# beaconboard3.net
KiCad netlist of a schematic drawn in EAGLE
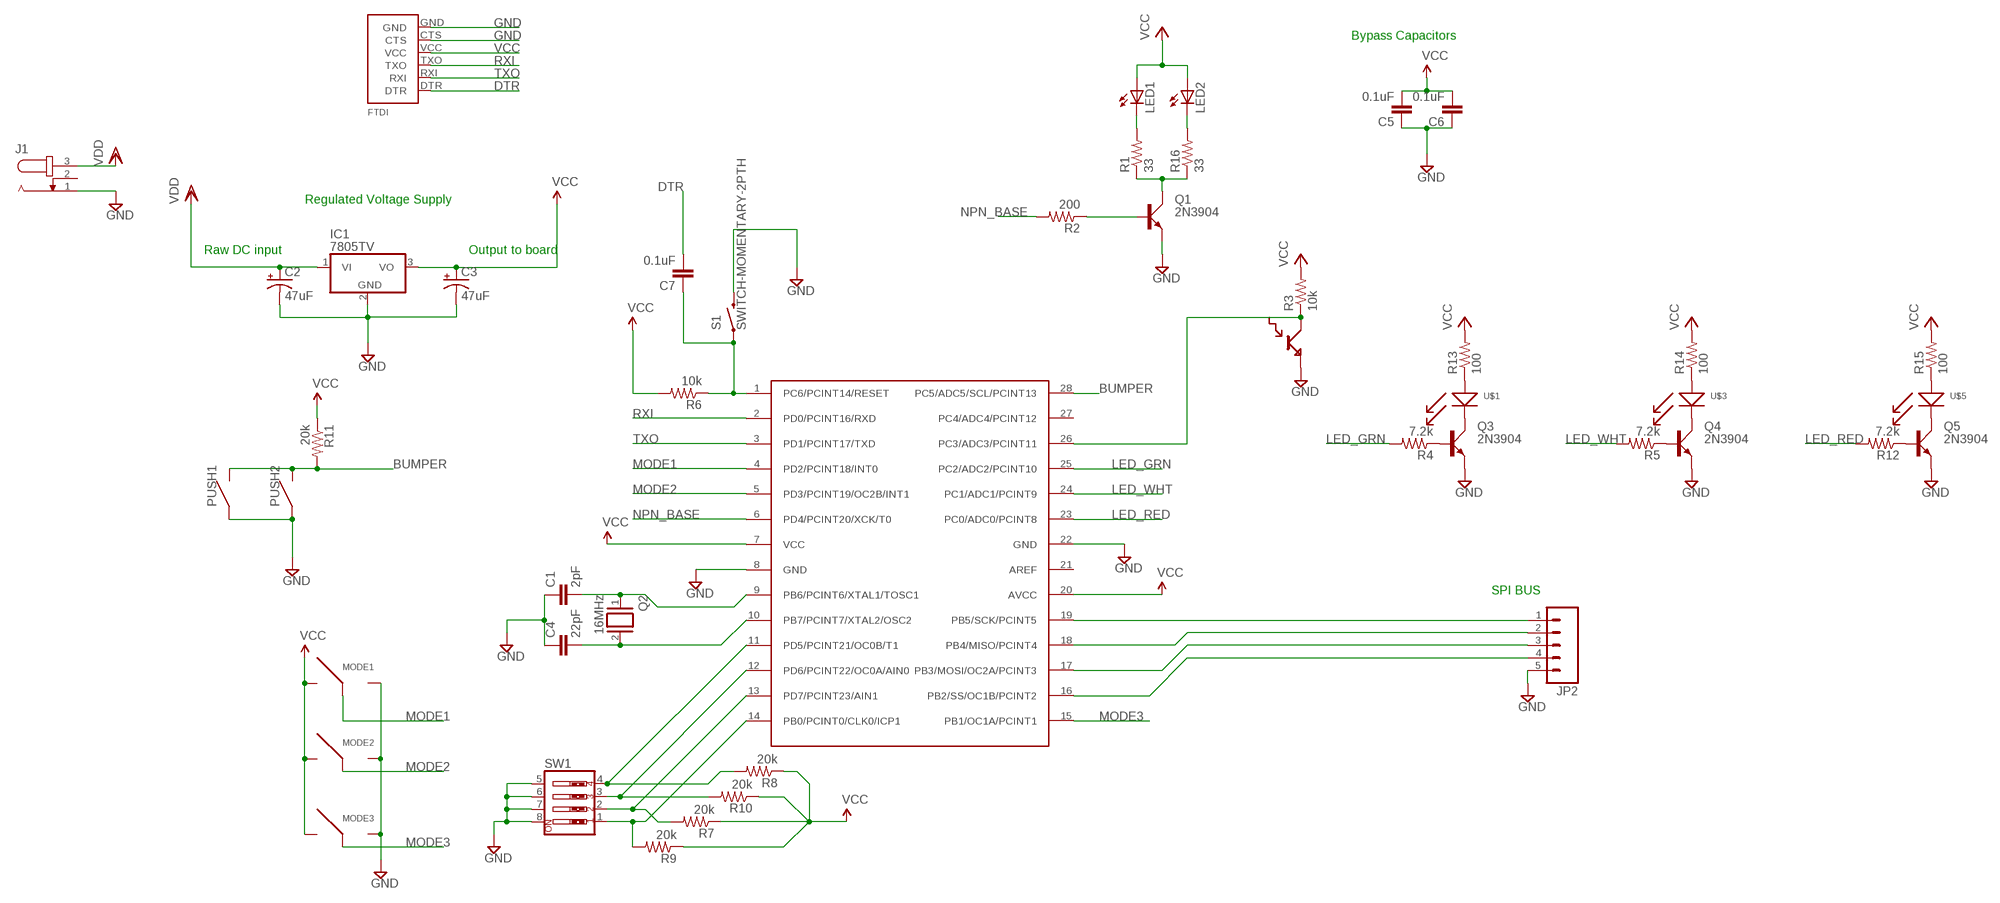
[diagram p0: schematic, sheet 1]

(export (version "E")
  (design (tool "Eeschema 10.0.6"))
  (components
    (comp (ref "C1")
      (value "2pF")
      (footprint "eagle-import:CAP-PTH-SMALL")
      (libsource (lib "eagle-import") (part "CAPPTH"))
    )
    (comp (ref "C2")
      (value "47uF")
      (footprint "eagle-import:CPOL-RADIAL-10UF-25V")
      (libsource (lib "eagle-import") (part "CAP_POLPTH2"))
    )
    (comp (ref "C3")
      (value "47uF")
      (footprint "eagle-import:CPOL-RADIAL-10UF-25V")
      (libsource (lib "eagle-import") (part "CAP_POLPTH2"))
    )
    (comp (ref "C4")
      (value "22pF")
      (footprint "eagle-import:CAP-PTH-SMALL")
      (libsource (lib "eagle-import") (part "CAPPTH"))
    )
    (comp (ref "C5")
      (value "0.1uF")
      (footprint "eagle-import:CAP-PTH-5MM")
      (libsource (lib "eagle-import") (part "CAPPTH1"))
    )
    (comp (ref "C6")
      (value "0.1uF")
      (footprint "eagle-import:CAP-PTH-5MM")
      (libsource (lib "eagle-import") (part "CAPPTH1"))
    )
    (comp (ref "C7")
      (value "0.1uF")
      (footprint "eagle-import:CAP-PTH-5MM")
      (libsource (lib "eagle-import") (part "CAPPTH1"))
    )
    (comp (ref "IC1")
      (value "7805TV")
      (footprint "eagle-import:TO220V")
      (libsource (lib "eagle-import") (part "78TV05"))
    )
    (comp (ref "J1")
      (value "JACK-PLUG1")
      (footprint "eagle-import:SPC4078")
      (libsource (lib "eagle-import") (part "JACK-PLUG1"))
    )
    (comp (ref "JP2")
      (value "M05LOCK_LONGPADS")
      (footprint "eagle-import:1X05_LOCK_LONGPADS")
      (libsource (lib "eagle-import") (part "M05LOCK_LONGPADS"))
    )
    (comp (ref "LED1")
      (value "LED-2AC-CP41B-WES")
      (footprint "eagle-import:CP41B")
      (libsource (lib "eagle-import") (part "LED-2AC-CP41B-WES"))
    )
    (comp (ref "LED2")
      (value "LED-2AC-CP41B-WES")
      (footprint "eagle-import:CP41B")
      (libsource (lib "eagle-import") (part "LED-2AC-CP41B-WES"))
    )
    (comp (ref "MODE1")
      (value "SPD_SLIDE_SWITCH")
      (footprint "eagle-import:SPDT_SLIDE_SWITCH")
      (libsource (lib "eagle-import") (part "SPD_SLIDE_SWITCH"))
    )
    (comp (ref "MODE2")
      (value "SPD_SLIDE_SWITCH")
      (footprint "eagle-import:SPDT_SLIDE_SWITCH")
      (libsource (lib "eagle-import") (part "SPD_SLIDE_SWITCH"))
    )
    (comp (ref "MODE3")
      (value "SPD_SLIDE_SWITCH")
      (footprint "eagle-import:SPDT_SLIDE_SWITCH")
      (libsource (lib "eagle-import") (part "SPD_SLIDE_SWITCH"))
    )
    (comp (ref "PUSH1")
      (value "D6_PUSHBUTTON")
      (footprint "eagle-import:D6_PUSH_BUTTON")
      (libsource (lib "eagle-import") (part "D6_PUSHBUTTON"))
    )
    (comp (ref "PUSH2")
      (value "D6_PUSHBUTTON")
      (footprint "eagle-import:D6_PUSH_BUTTON")
      (libsource (lib "eagle-import") (part "D6_PUSHBUTTON"))
    )
    (comp (ref "Q1")
      (value "2N3904")
      (footprint "eagle-import:TO92D")
      (libsource (lib "eagle-import") (part "2N3904"))
    )
    (comp (ref "Q2")
      (value "16MHz")
      (footprint "eagle-import:QS")
      (libsource (lib "eagle-import") (part "XTAL/S"))
    )
    (comp (ref "Q3")
      (value "2N3904")
      (footprint "eagle-import:TO92D")
      (libsource (lib "eagle-import") (part "2N3904"))
    )
    (comp (ref "Q4")
      (value "2N3904")
      (footprint "eagle-import:TO92D")
      (libsource (lib "eagle-import") (part "2N3904"))
    )
    (comp (ref "Q5")
      (value "2N3904")
      (footprint "eagle-import:TO92D")
      (libsource (lib "eagle-import") (part "2N3904"))
    )
    (comp (ref "R1")
      (value "33")
      (footprint "eagle-import:AXIAL-0.4")
      (libsource (lib "eagle-import") (part "RESISTORPTH-1/4W"))
    )
    (comp (ref "R2")
      (value "200")
      (footprint "eagle-import:AXIAL-0.4")
      (libsource (lib "eagle-import") (part "RESISTORPTH-1/4W"))
    )
    (comp (ref "R3")
      (value "10k")
      (footprint "eagle-import:AXIAL-0.4")
      (libsource (lib "eagle-import") (part "RESISTORPTH-1/4W"))
    )
    (comp (ref "R4")
      (value "7.2k")
      (footprint "eagle-import:AXIAL-0.4")
      (libsource (lib "eagle-import") (part "RESISTORPTH-1/4W"))
    )
    (comp (ref "R5")
      (value "7.2k")
      (footprint "eagle-import:AXIAL-0.4")
      (libsource (lib "eagle-import") (part "RESISTORPTH-1/4W"))
    )
    (comp (ref "R6")
      (value "10k")
      (footprint "eagle-import:AXIAL-0.4")
      (libsource (lib "eagle-import") (part "RESISTORPTH-1/4W"))
    )
    (comp (ref "R7")
      (value "20k")
      (footprint "eagle-import:AXIAL-0.4")
      (libsource (lib "eagle-import") (part "RESISTORPTH-1/4W"))
    )
    (comp (ref "R8")
      (value "20k")
      (footprint "eagle-import:AXIAL-0.4")
      (libsource (lib "eagle-import") (part "RESISTORPTH-1/4W"))
    )
    (comp (ref "R9")
      (value "20k")
      (footprint "eagle-import:AXIAL-0.4")
      (libsource (lib "eagle-import") (part "RESISTORPTH-1/4W"))
    )
    (comp (ref "R10")
      (value "20k")
      (footprint "eagle-import:AXIAL-0.4")
      (libsource (lib "eagle-import") (part "RESISTORPTH-1/4W"))
    )
    (comp (ref "R11")
      (value "20k")
      (footprint "eagle-import:AXIAL-0.4")
      (libsource (lib "eagle-import") (part "RESISTORPTH-1/4W"))
    )
    (comp (ref "R12")
      (value "7.2k")
      (footprint "eagle-import:AXIAL-0.4")
      (libsource (lib "eagle-import") (part "RESISTORPTH-1/4W"))
    )
    (comp (ref "R13")
      (value "100")
      (footprint "eagle-import:AXIAL-0.4")
      (libsource (lib "eagle-import") (part "RESISTORPTH-1/4W"))
    )
    (comp (ref "R14")
      (value "100")
      (footprint "eagle-import:AXIAL-0.4")
      (libsource (lib "eagle-import") (part "RESISTORPTH-1/4W"))
    )
    (comp (ref "R15")
      (value "100")
      (footprint "eagle-import:AXIAL-0.4")
      (libsource (lib "eagle-import") (part "RESISTORPTH-1/4W"))
    )
    (comp (ref "R16")
      (value "33")
      (footprint "eagle-import:AXIAL-0.4")
      (libsource (lib "eagle-import") (part "RESISTORPTH-1/4W"))
    )
    (comp (ref "S1")
      (value "SWITCH-MOMENTARY-2PTH")
      (footprint "eagle-import:TACTILE-PTH")
      (libsource (lib "eagle-import") (part "SWITCH-MOMENTARY-2PTH"))
    )
    (comp (ref "SW1")
      (value "SW_DIP-4")
      (footprint "eagle-import:EDG-04")
      (libsource (lib "eagle-import") (part "SW_DIP-4"))
    )
    (comp (ref "U$1")
      (value "8MM_LED")
      (footprint "eagle-import:8MM_LED")
      (libsource (lib "eagle-import") (part "8MM_LED"))
    )
    (comp (ref "U$2")
      (value "BPW77NA")
      (footprint "eagle-import:TO-18")
      (libsource (lib "eagle-import") (part "BPW77NA"))
    )
    (comp (ref "U$3")
      (value "8MM_LED")
      (footprint "eagle-import:8MM_LED")
      (libsource (lib "eagle-import") (part "8MM_LED"))
    )
    (comp (ref "U$4")
      (value "ATMEGA328")
      (footprint "eagle-import:DIL28-3")
      (libsource (lib "eagle-import") (part "ATMEGA328"))
    )
    (comp (ref "U$5")
      (value "8MM_LED")
      (footprint "eagle-import:8MM_LED")
      (libsource (lib "eagle-import") (part "8MM_LED"))
    )
    (comp (ref "U$6")
      (value "FTDI")
      (footprint "eagle-import:FTDI")
      (libsource (lib "eagle-import") (part "FTDI"))
    )
  )
  (nets
    (net (code "1") (name "/BUMPER") (class "Default")
      (node (ref "PUSH1") (pin "3") (pinfunction "2_3") (pintype "bidirectional"))
      (node (ref "PUSH1") (pin "4") (pinfunction "2_4") (pintype "bidirectional"))
      (node (ref "PUSH2") (pin "3") (pinfunction "2_3") (pintype "bidirectional"))
      (node (ref "PUSH2") (pin "4") (pinfunction "2_4") (pintype "bidirectional"))
      (node (ref "R11") (pin "P$2") (pinfunction "2_P$2") (pintype "passive"))
      (node (ref "U$4") (pin "28") (pinfunction "PC5/ADC5/SCL/PCINT13_28") (pintype "bidirectional"))
    )
    (net (code "2") (name "/DTR") (class "Default")
      (node (ref "C7") (pin "2") (pinfunction "2_2") (pintype "passive"))
      (node (ref "U$6") (pin "DTR") (pinfunction "DTR_DTR") (pintype "bidirectional"))
    )
    (net (code "3") (name "/LED_GRN") (class "Default")
      (node (ref "R4") (pin "P$2") (pinfunction "2_P$2") (pintype "passive"))
      (node (ref "U$4") (pin "25") (pinfunction "PC2/ADC2/PCINT10_25") (pintype "bidirectional"))
    )
    (net (code "4") (name "/LED_RED") (class "Default")
      (node (ref "R12") (pin "P$2") (pinfunction "2_P$2") (pintype "passive"))
      (node (ref "U$4") (pin "23") (pinfunction "PC0/ADC0/PCINT8_23") (pintype "bidirectional"))
    )
    (net (code "5") (name "/LED_WHT") (class "Default")
      (node (ref "R5") (pin "P$2") (pinfunction "2_P$2") (pintype "passive"))
      (node (ref "U$4") (pin "24") (pinfunction "PC1/ADC1/PCINT9_24") (pintype "bidirectional"))
    )
    (net (code "6") (name "/MODE1") (class "Default")
      (node (ref "MODE1") (pin "2") (pinfunction "2_2") (pintype "bidirectional"))
      (node (ref "U$4") (pin "4") (pinfunction "PD2/PCINT18/INT0_4") (pintype "bidirectional"))
    )
    (net (code "7") (name "/MODE2") (class "Default")
      (node (ref "MODE2") (pin "2") (pinfunction "2_2") (pintype "bidirectional"))
      (node (ref "U$4") (pin "5") (pinfunction "PD3/PCINT19/OC2B/INT1_5") (pintype "bidirectional"))
    )
    (net (code "8") (name "/MODE3") (class "Default")
      (node (ref "MODE3") (pin "2") (pinfunction "2_2") (pintype "bidirectional"))
      (node (ref "U$4") (pin "15") (pinfunction "PB1/OC1A/PCINT1_15") (pintype "bidirectional"))
    )
    (net (code "9") (name "/NPN_BASE") (class "Default")
      (node (ref "R2") (pin "P$2") (pinfunction "2_P$2") (pintype "passive"))
      (node (ref "U$4") (pin "6") (pinfunction "PD4/PCINT20/XCK/T0_6") (pintype "bidirectional"))
    )
    (net (code "10") (name "/RXI") (class "Default")
      (node (ref "U$4") (pin "2") (pinfunction "PD0/PCINT16/RXD_2") (pintype "bidirectional"))
      (node (ref "U$6") (pin "TXO") (pinfunction "TXO_TXO") (pintype "bidirectional"))
    )
    (net (code "11") (name "/TXO") (class "Default")
      (node (ref "U$4") (pin "3") (pinfunction "PD1/PCINT17/TXD_3") (pintype "bidirectional"))
      (node (ref "U$6") (pin "RXI") (pinfunction "RXI_RXI") (pintype "bidirectional"))
    )
    (net (code "12") (name "GND") (class "Default")
      (node (ref "C1") (pin "1") (pinfunction "1_1") (pintype "passive"))
      (node (ref "C2") (pin "2") (pinfunction "-_2") (pintype "passive"))
      (node (ref "C3") (pin "2") (pinfunction "-_2") (pintype "passive"))
      (node (ref "C4") (pin "1") (pinfunction "1_1") (pintype "passive"))
      (node (ref "C5") (pin "1") (pinfunction "1_1") (pintype "passive"))
      (node (ref "C6") (pin "1") (pinfunction "1_1") (pintype "passive"))
      (node (ref "IC1") (pin "2") (pinfunction "GND_2") (pintype "passive"))
      (node (ref "J1") (pin "1") (pinfunction "1_1") (pintype "passive"))
      (node (ref "JP2") (pin "5") (pinfunction "5_5") (pintype "passive"))
      (node (ref "MODE1") (pin "3") (pinfunction "3_3") (pintype "bidirectional"))
      (node (ref "MODE2") (pin "3") (pinfunction "3_3") (pintype "bidirectional"))
      (node (ref "MODE3") (pin "3") (pinfunction "3_3") (pintype "bidirectional"))
      (node (ref "PUSH1") (pin "1") (pinfunction "1_1") (pintype "bidirectional"))
      (node (ref "PUSH1") (pin "2") (pinfunction "1_2") (pintype "bidirectional"))
      (node (ref "PUSH2") (pin "1") (pinfunction "1_1") (pintype "bidirectional"))
      (node (ref "PUSH2") (pin "2") (pinfunction "1_2") (pintype "bidirectional"))
      (node (ref "Q1") (pin "E") (pinfunction "E_E") (pintype "passive"))
      (node (ref "Q3") (pin "E") (pinfunction "E_E") (pintype "passive"))
      (node (ref "Q4") (pin "E") (pinfunction "E_E") (pintype "passive"))
      (node (ref "Q5") (pin "E") (pinfunction "E_E") (pintype "passive"))
      (node (ref "S1") (pin "3") (pinfunction "2_3") (pintype "passive"))
      (node (ref "SW1") (pin "5") (pinfunction "5_5") (pintype "passive"))
      (node (ref "SW1") (pin "6") (pinfunction "6_6") (pintype "passive"))
      (node (ref "SW1") (pin "7") (pinfunction "7_7") (pintype "passive"))
      (node (ref "SW1") (pin "8") (pinfunction "8_8") (pintype "passive"))
      (node (ref "U$2") (pin "E") (pinfunction "E_E") (pintype "bidirectional"))
      (node (ref "U$4") (pin "22") (pinfunction "GND_22") (pintype "power_in"))
      (node (ref "U$4") (pin "8") (pinfunction "GND_8") (pintype "power_in"))
      (node (ref "U$6") (pin "CTS") (pinfunction "CTS_CTS") (pintype "bidirectional"))
      (node (ref "U$6") (pin "GND") (pinfunction "GND_GND") (pintype "bidirectional"))
    )
    (net (code "13") (name "Net-(Q3-PadC)") (class "Default")
      (node (ref "Q3") (pin "C") (pinfunction "C_C") (pintype "passive"))
      (node (ref "U$1") (pin "NEG") (pinfunction "NEG_NEG") (pintype "bidirectional"))
    )
    (net (code "14") (name "Net-(Q4-PadC)") (class "Default")
      (node (ref "Q4") (pin "C") (pinfunction "C_C") (pintype "passive"))
      (node (ref "U$3") (pin "NEG") (pinfunction "NEG_NEG") (pintype "bidirectional"))
    )
    (net (code "15") (name "Net-(Q5-PadC)") (class "Default")
      (node (ref "Q5") (pin "C") (pinfunction "C_C") (pintype "passive"))
      (node (ref "U$5") (pin "NEG") (pinfunction "NEG_NEG") (pintype "bidirectional"))
    )
    (net (code "16") (name "Net-(R1-1)") (class "Default")
      (node (ref "Q1") (pin "C") (pinfunction "C_C") (pintype "passive"))
      (node (ref "R1") (pin "P$1") (pinfunction "1_P$1") (pintype "passive"))
      (node (ref "R16") (pin "P$1") (pinfunction "1_P$1") (pintype "passive"))
    )
    (net (code "17") (name "Net-(R1-2)") (class "Default")
      (node (ref "LED1") (pin "1") (pinfunction "C_1") (pintype "passive"))
      (node (ref "LED1") (pin "4") (pinfunction "C_4") (pintype "passive"))
      (node (ref "R1") (pin "P$2") (pinfunction "2_P$2") (pintype "passive"))
    )
    (net (code "18") (name "Net-(R2-1)") (class "Default")
      (node (ref "Q1") (pin "B") (pinfunction "B_B") (pintype "passive"))
      (node (ref "R2") (pin "P$1") (pinfunction "1_P$1") (pintype "passive"))
    )
    (net (code "19") (name "Net-(R3-1)") (class "Default")
      (node (ref "R3") (pin "P$1") (pinfunction "1_P$1") (pintype "passive"))
      (node (ref "U$2") (pin "C") (pinfunction "C_C") (pintype "bidirectional"))
      (node (ref "U$4") (pin "26") (pinfunction "PC3/ADC3/PCINT11_26") (pintype "bidirectional"))
    )
    (net (code "20") (name "Net-(R4-1)") (class "Default")
      (node (ref "Q3") (pin "B") (pinfunction "B_B") (pintype "passive"))
      (node (ref "R4") (pin "P$1") (pinfunction "1_P$1") (pintype "passive"))
    )
    (net (code "21") (name "Net-(R5-1)") (class "Default")
      (node (ref "Q4") (pin "B") (pinfunction "B_B") (pintype "passive"))
      (node (ref "R5") (pin "P$1") (pinfunction "1_P$1") (pintype "passive"))
    )
    (net (code "22") (name "Net-(R6-1)") (class "Default")
      (node (ref "C7") (pin "1") (pinfunction "1_1") (pintype "passive"))
      (node (ref "R6") (pin "P$1") (pinfunction "1_P$1") (pintype "passive"))
      (node (ref "S1") (pin "1") (pinfunction "1_1") (pintype "passive"))
      (node (ref "U$4") (pin "1") (pinfunction "PC6/PCINT14/RESET_1") (pintype "bidirectional"))
    )
    (net (code "23") (name "Net-(R7-2)") (class "Default")
      (node (ref "R7") (pin "P$2") (pinfunction "2_P$2") (pintype "passive"))
      (node (ref "SW1") (pin "2") (pinfunction "2_2") (pintype "passive"))
      (node (ref "U$4") (pin "13") (pinfunction "PD7/PCINT23/AIN1_13") (pintype "bidirectional"))
    )
    (net (code "24") (name "Net-(R8-2)") (class "Default")
      (node (ref "R8") (pin "P$2") (pinfunction "2_P$2") (pintype "passive"))
      (node (ref "SW1") (pin "4") (pinfunction "4_4") (pintype "passive"))
      (node (ref "U$4") (pin "11") (pinfunction "PD5/PCINT21/OC0B/T1_11") (pintype "bidirectional"))
    )
    (net (code "25") (name "Net-(R9-2)") (class "Default")
      (node (ref "R9") (pin "P$2") (pinfunction "2_P$2") (pintype "passive"))
      (node (ref "SW1") (pin "1") (pinfunction "1_1") (pintype "passive"))
      (node (ref "U$4") (pin "14") (pinfunction "PB0/PCINT0/CLK0/ICP1_14") (pintype "bidirectional"))
    )
    (net (code "26") (name "Net-(R10-2)") (class "Default")
      (node (ref "R10") (pin "P$2") (pinfunction "2_P$2") (pintype "passive"))
      (node (ref "SW1") (pin "3") (pinfunction "3_3") (pintype "passive"))
      (node (ref "U$4") (pin "12") (pinfunction "PD6/PCINT22/OC0A/AIN0_12") (pintype "bidirectional"))
    )
    (net (code "27") (name "Net-(R12-1)") (class "Default")
      (node (ref "Q5") (pin "B") (pinfunction "B_B") (pintype "passive"))
      (node (ref "R12") (pin "P$1") (pinfunction "1_P$1") (pintype "passive"))
    )
    (net (code "28") (name "Net-(R13-1)") (class "Default")
      (node (ref "R13") (pin "P$1") (pinfunction "1_P$1") (pintype "passive"))
      (node (ref "U$1") (pin "POS") (pinfunction "POS_POS") (pintype "bidirectional"))
    )
    (net (code "29") (name "Net-(R14-1)") (class "Default")
      (node (ref "R14") (pin "P$1") (pinfunction "1_P$1") (pintype "passive"))
      (node (ref "U$3") (pin "POS") (pinfunction "POS_POS") (pintype "bidirectional"))
    )
    (net (code "30") (name "Net-(R15-1)") (class "Default")
      (node (ref "R15") (pin "P$1") (pinfunction "1_P$1") (pintype "passive"))
      (node (ref "U$5") (pin "POS") (pinfunction "POS_POS") (pintype "bidirectional"))
    )
    (net (code "31") (name "Net-(R16-2)") (class "Default")
      (node (ref "LED2") (pin "1") (pinfunction "C_1") (pintype "passive"))
      (node (ref "LED2") (pin "4") (pinfunction "C_4") (pintype "passive"))
      (node (ref "R16") (pin "P$2") (pinfunction "2_P$2") (pintype "passive"))
    )
    (net (code "32") (name "Net-(U$4-PB2{slash}SS{slash}OC1B{slash}PCINT2)") (class "Default")
      (node (ref "JP2") (pin "4") (pinfunction "4_4") (pintype "passive"))
      (node (ref "U$4") (pin "16") (pinfunction "PB2/SS/OC1B/PCINT2_16") (pintype "bidirectional"))
    )
    (net (code "33") (name "Net-(U$4-PB3{slash}MOSI{slash}OC2A{slash}PCINT3)") (class "Default")
      (node (ref "JP2") (pin "3") (pinfunction "3_3") (pintype "passive"))
      (node (ref "U$4") (pin "17") (pinfunction "PB3/MOSI/OC2A/PCINT3_17") (pintype "bidirectional"))
    )
    (net (code "34") (name "Net-(U$4-PB4{slash}MISO{slash}PCINT4)") (class "Default")
      (node (ref "JP2") (pin "2") (pinfunction "2_2") (pintype "passive"))
      (node (ref "U$4") (pin "18") (pinfunction "PB4/MISO/PCINT4_18") (pintype "bidirectional"))
    )
    (net (code "35") (name "Net-(U$4-PB5{slash}SCK{slash}PCINT5)") (class "Default")
      (node (ref "JP2") (pin "1") (pinfunction "1_1") (pintype "passive"))
      (node (ref "U$4") (pin "19") (pinfunction "PB5/SCK/PCINT5_19") (pintype "bidirectional"))
    )
    (net (code "36") (name "Net-(U$4-PB6{slash}PCINT6{slash}XTAL1{slash}TOSC1)") (class "Default")
      (node (ref "C1") (pin "2") (pinfunction "2_2") (pintype "passive"))
      (node (ref "Q2") (pin "1") (pinfunction "1_1") (pintype "passive"))
      (node (ref "U$4") (pin "9") (pinfunction "PB6/PCINT6/XTAL1/TOSC1_9") (pintype "bidirectional"))
    )
    (net (code "37") (name "Net-(U$4-PB7{slash}PCINT7{slash}XTAL2{slash}OSC2)") (class "Default")
      (node (ref "C4") (pin "2") (pinfunction "2_2") (pintype "passive"))
      (node (ref "Q2") (pin "2") (pinfunction "2_2") (pintype "passive"))
      (node (ref "U$4") (pin "10") (pinfunction "PB7/PCINT7/XTAL2/OSC2_10") (pintype "bidirectional"))
    )
    (net (code "38") (name "VCC") (class "Default")
      (node (ref "C3") (pin "1") (pinfunction "+_1") (pintype "passive"))
      (node (ref "C5") (pin "2") (pinfunction "2_2") (pintype "passive"))
      (node (ref "C6") (pin "2") (pinfunction "2_2") (pintype "passive"))
      (node (ref "IC1") (pin "3") (pinfunction "VO_3") (pintype "passive"))
      (node (ref "LED1") (pin "2") (pinfunction "A_2") (pintype "passive"))
      (node (ref "LED1") (pin "3") (pinfunction "A_3") (pintype "passive"))
      (node (ref "LED2") (pin "2") (pinfunction "A_2") (pintype "passive"))
      (node (ref "LED2") (pin "3") (pinfunction "A_3") (pintype "passive"))
      (node (ref "MODE1") (pin "1") (pinfunction "1_1") (pintype "bidirectional"))
      (node (ref "MODE2") (pin "1") (pinfunction "1_1") (pintype "bidirectional"))
      (node (ref "MODE3") (pin "1") (pinfunction "1_1") (pintype "bidirectional"))
      (node (ref "R10") (pin "P$1") (pinfunction "1_P$1") (pintype "passive"))
      (node (ref "R11") (pin "P$1") (pinfunction "1_P$1") (pintype "passive"))
      (node (ref "R13") (pin "P$2") (pinfunction "2_P$2") (pintype "passive"))
      (node (ref "R14") (pin "P$2") (pinfunction "2_P$2") (pintype "passive"))
      (node (ref "R15") (pin "P$2") (pinfunction "2_P$2") (pintype "passive"))
      (node (ref "R3") (pin "P$2") (pinfunction "2_P$2") (pintype "passive"))
      (node (ref "R6") (pin "P$2") (pinfunction "2_P$2") (pintype "passive"))
      (node (ref "R7") (pin "P$1") (pinfunction "1_P$1") (pintype "passive"))
      (node (ref "R8") (pin "P$1") (pinfunction "1_P$1") (pintype "passive"))
      (node (ref "R9") (pin "P$1") (pinfunction "1_P$1") (pintype "passive"))
      (node (ref "U$4") (pin "20") (pinfunction "AVCC_20") (pintype "bidirectional"))
      (node (ref "U$4") (pin "7") (pinfunction "VCC_7") (pintype "power_in"))
      (node (ref "U$6") (pin "VCC") (pinfunction "VCC_VCC") (pintype "bidirectional"))
    )
    (net (code "39") (name "VDD") (class "Default")
      (node (ref "C2") (pin "1") (pinfunction "+_1") (pintype "passive"))
      (node (ref "IC1") (pin "1") (pinfunction "VI_1") (pintype "input"))
      (node (ref "J1") (pin "3") (pinfunction "3_3") (pintype "passive"))
    )
    (net (code "40") (name "unconnected-(J1-Pad2)") (class "Default")
      (node (ref "J1") (pin "2") (pinfunction "2_2") (pintype "passive"))
    )
    (net (code "41") (name "unconnected-(U$4-AREF-Pad21)") (class "Default")
      (node (ref "U$4") (pin "21") (pinfunction "AREF_21") (pintype "bidirectional"))
    )
    (net (code "42") (name "unconnected-(U$4-PC4{slash}ADC4{slash}PCINT12-Pad27)") (class "Default")
      (node (ref "U$4") (pin "27") (pinfunction "PC4/ADC4/PCINT12_27") (pintype "bidirectional"))
    )
  )
)
